# ADC.net
KiCad netlist of a schematic drawn in Altium Designer
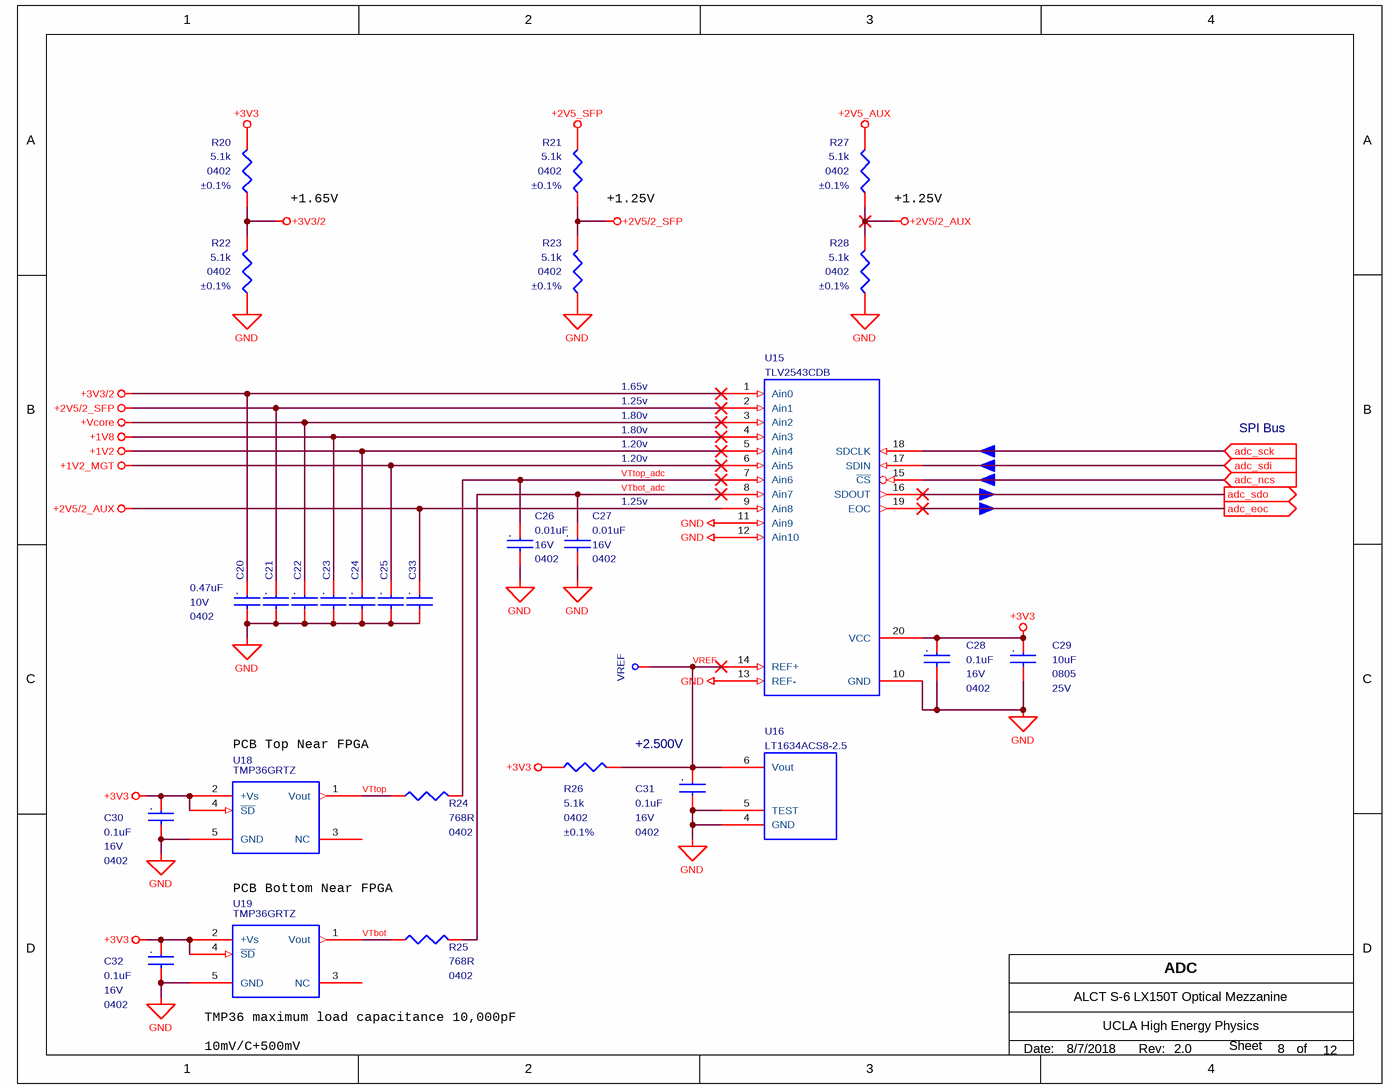
[diagram p0: ADC.SchDoc]

(export (version "E")
  (design (tool "Eeschema 10.0.6"))
  (components
    (comp (ref "C20")
      (value "0.47uF")
      (footprint "MC_S6/SM/C_0402_IPC")
      (description "CAP CER 0.47UF 10V X5R 0402")
      (fields
        (field (name "MANUFACTURER") "Murata Electronics North America")
        (field (name "MANUFACTURER PART NUMBER") "GRM155R61A474KE15J")
        (field (name "PACKAGE") "0402")
        (field (name "VOLTAGE - RATED") "10V")
      )
      (libsource (lib "ALCT_MEZ_SPARTAN6_Library") (part "GRM155R61A474KE15J"))
    )
    (comp (ref "C21")
      (value "0.47uF")
      (footprint "MC_S6/SM/C_0402_IPC")
      (description "CAP CER 0.47UF 10V X5R 0402")
      (fields
        (field (name "MANUFACTURER") "Murata Electronics North America")
        (field (name "MANUFACTURER PART NUMBER") "GRM155R61A474KE15J")
      )
      (libsource (lib "ALCT_MEZ_SPARTAN6_Library") (part "GRM155R61A474KE15J"))
    )
    (comp (ref "C22")
      (value "0.47uF")
      (footprint "MC_S6/SM/C_0402_IPC")
      (description "CAP CER 0.47UF 10V X5R 0402")
      (fields
        (field (name "MANUFACTURER") "Murata Electronics North America")
        (field (name "MANUFACTURER PART NUMBER") "GRM155R61A474KE15J")
      )
      (libsource (lib "ALCT_MEZ_SPARTAN6_Library") (part "GRM155R61A474KE15J"))
    )
    (comp (ref "C23")
      (value "0.47uF")
      (footprint "MC_S6/SM/C_0402_IPC")
      (description "CAP CER 0.47UF 10V X5R 0402")
      (fields
        (field (name "MANUFACTURER") "Murata Electronics North America")
        (field (name "MANUFACTURER PART NUMBER") "GRM155R61A474KE15J")
      )
      (libsource (lib "ALCT_MEZ_SPARTAN6_Library") (part "GRM155R61A474KE15J"))
    )
    (comp (ref "C24")
      (value "0.47uF")
      (footprint "MC_S6/SM/C_0402_IPC")
      (description "CAP CER 0.47UF 10V X5R 0402")
      (fields
        (field (name "MANUFACTURER") "Murata Electronics North America")
        (field (name "MANUFACTURER PART NUMBER") "GRM155R61A474KE15J")
      )
      (libsource (lib "ALCT_MEZ_SPARTAN6_Library") (part "GRM155R61A474KE15J"))
    )
    (comp (ref "C25")
      (value "0.47uF")
      (footprint "MC_S6/SM/C_0402_IPC")
      (description "CAP CER 0.47UF 10V X5R 0402")
      (fields
        (field (name "MANUFACTURER") "Murata Electronics North America")
        (field (name "MANUFACTURER PART NUMBER") "GRM155R61A474KE15J")
      )
      (libsource (lib "ALCT_MEZ_SPARTAN6_Library") (part "GRM155R61A474KE15J"))
    )
    (comp (ref "C26")
      (value "0.01uF")
      (footprint "MC_S6/SM/C_0402_IPC")
      (description "CAP CER 10nF 16V X7R 0402")
      (fields
        (field (name "MANUFACTURER") "KEMET")
        (field (name "MANUFACTURER PART NUMBER") "C0402C103K4RACTU")
        (field (name "VOLTAGE - RATED") "16V")
        (field (name "PACKAGE") "0402")
      )
      (libsource (lib "ALCT_MEZ_SPARTAN6_Library") (part "C0402C103K4RACTU"))
    )
    (comp (ref "C27")
      (value "0.01uF")
      (footprint "MC_S6/SM/C_0402_IPC")
      (description "CAP CER 10nF 16V X7R 0402")
      (fields
        (field (name "MANUFACTURER") "KEMET")
        (field (name "MANUFACTURER PART NUMBER") "C0402C103K4RACTU")
        (field (name "VOLTAGE - RATED") "16V")
        (field (name "PACKAGE") "0402")
      )
      (libsource (lib "ALCT_MEZ_SPARTAN6_Library") (part "C0402C103K4RACTU"))
    )
    (comp (ref "C28")
      (value "0.1uF")
      (footprint "MC_S6/SM/C_0402_IPC")
      (description "CAP CER 0.1UF 16V X7R 0402")
      (fields
        (field (name "MANUFACTURER") "KEMET")
        (field (name "MANUFACTURER PART NUMBER") "C0402C104K4RACTU")
        (field (name "PACKAGE") "0402")
        (field (name "VOLTAGE - RATED") "16V")
      )
      (libsource (lib "ALCT_MEZ_SPARTAN6_Library") (part "C0402C104K4RACTU"))
    )
    (comp (ref "C29")
      (value "10uF")
      (footprint "MC_S6/SM/C_0805_IPC")
      (description "CAP CER 10UF 25V X5R 0805")
      (fields
        (field (name "MANUFACTURER") "Murata Electronics North America")
        (field (name "MANUFACTURER PART NUMBER") "GRM21BR61E106KA73L")
        (field (name "VOLTAGE - RATED") "25V")
        (field (name "PACKAGE") "0805")
      )
      (libsource (lib "ALCT_MEZ_SPARTAN6_Library") (part "GRM21BR61E106KA73L"))
    )
    (comp (ref "C30")
      (value "0.1uF")
      (footprint "MC_S6/SM/C_0402_IPC")
      (description "CAP CER 0.1UF 16V X7R 0402")
      (fields
        (field (name "MANUFACTURER") "KEMET")
        (field (name "MANUFACTURER PART NUMBER") "C0402C104K4RACTU")
        (field (name "PACKAGE") "0402")
        (field (name "VOLTAGE - RATED") "16V")
      )
      (libsource (lib "ALCT_MEZ_SPARTAN6_Library") (part "C0402C104K4RACTU"))
    )
    (comp (ref "C31")
      (value "0.1uF")
      (footprint "MC_S6/SM/C_0402_IPC")
      (description "CAP CER 0.1UF 16V X7R 0402")
      (fields
        (field (name "MANUFACTURER") "KEMET")
        (field (name "MANUFACTURER PART NUMBER") "C0402C104K4RACTU")
        (field (name "PACKAGE") "0402")
        (field (name "VOLTAGE - RATED") "16V")
      )
      (libsource (lib "ALCT_MEZ_SPARTAN6_Library") (part "C0402C104K4RACTU"))
    )
    (comp (ref "C32")
      (value "0.1uF")
      (footprint "MC_S6/SM/C_0402_IPC")
      (description "CAP CER 0.1UF 16V X7R 0402")
      (fields
        (field (name "MANUFACTURER") "KEMET")
        (field (name "MANUFACTURER PART NUMBER") "C0402C104K4RACTU")
        (field (name "PACKAGE") "0402")
        (field (name "VOLTAGE - RATED") "16V")
      )
      (libsource (lib "ALCT_MEZ_SPARTAN6_Library") (part "C0402C104K4RACTU"))
    )
    (comp (ref "C33")
      (value "0.47uF")
      (footprint "MC_S6/SM/C_0402_IPC")
      (description "CAP CER 0.47UF 10V X5R 0402")
      (fields
        (field (name "MANUFACTURER") "Murata Electronics North America")
        (field (name "MANUFACTURER PART NUMBER") "GRM155R61A474KE15J")
      )
      (libsource (lib "ALCT_MEZ_SPARTAN6_Library") (part "GRM155R61A474KE15J"))
    )
    (comp (ref "R20")
      (value "5.1k")
      (footprint "MC_S6/SM/R_0402_IPC")
      (description "RES SMD 5.1K OHM 0.1% 1/16W 0402")
      (fields
        (field (name "TOLERANCE") "±0.1%")
        (field (name "MANUFACTURER") "Panasonic Electronic Components")
        (field (name "MANUFACTURER PART NUMBER") "ERA-2AEB512X")
        (field (name "SUPPLIER DEVICE PACKAGE") "0402")
      )
      (libsource (lib "ALCT_MEZ_SPARTAN6_Library") (part "ERA-2AEB512X"))
    )
    (comp (ref "R21")
      (value "5.1k")
      (footprint "MC_S6/SM/R_0402_IPC")
      (description "RES SMD 5.1K OHM 0.1% 1/16W 0402")
      (fields
        (field (name "TOLERANCE") "±0.1%")
        (field (name "MANUFACTURER") "Panasonic Electronic Components")
        (field (name "MANUFACTURER PART NUMBER") "ERA-2AEB512X")
        (field (name "SUPPLIER DEVICE PACKAGE") "0402")
      )
      (libsource (lib "ALCT_MEZ_SPARTAN6_Library") (part "ERA-2AEB512X"))
    )
    (comp (ref "R22")
      (value "5.1k")
      (footprint "MC_S6/SM/R_0402_IPC")
      (description "RES SMD 5.1K OHM 0.1% 1/16W 0402")
      (fields
        (field (name "TOLERANCE") "±0.1%")
        (field (name "MANUFACTURER") "Panasonic Electronic Components")
        (field (name "MANUFACTURER PART NUMBER") "ERA-2AEB512X")
        (field (name "SUPPLIER DEVICE PACKAGE") "0402")
      )
      (libsource (lib "ALCT_MEZ_SPARTAN6_Library") (part "ERA-2AEB512X"))
    )
    (comp (ref "R23")
      (value "5.1k")
      (footprint "MC_S6/SM/R_0402_IPC")
      (description "RES SMD 5.1K OHM 0.1% 1/16W 0402")
      (fields
        (field (name "TOLERANCE") "±0.1%")
        (field (name "MANUFACTURER") "Panasonic Electronic Components")
        (field (name "MANUFACTURER PART NUMBER") "ERA-2AEB512X")
        (field (name "SUPPLIER DEVICE PACKAGE") "0402")
      )
      (libsource (lib "ALCT_MEZ_SPARTAN6_Library") (part "ERA-2AEB512X"))
    )
    (comp (ref "R24")
      (value "768R")
      (footprint "MC_S6/SM/R_0402_IPC")
      (description "RES SMD 768 OHM 5.0% 1/10W 0402")
      (fields
        (field (name "MANUFACTURER") "Panasonic Electronic Components")
        (field (name "MANUFACTURER PART NUMBER") "ERJ-2RKF7680X")
        (field (name "SUPPLIER DEVICE PACKAGE") "0402")
      )
      (libsource (lib "ALCT_MEZ_SPARTAN6_Library") (part "ERJ-2RKF7680X"))
    )
    (comp (ref "R25")
      (value "768R")
      (footprint "MC_S6/SM/R_0402_IPC")
      (description "RES SMD 768 OHM 5.0% 1/10W 0402")
      (fields
        (field (name "TOLERANCE") "±1%")
        (field (name "MANUFACTURER") "Panasonic Electronic Components")
        (field (name "SUPPLIER DEVICE PACKAGE") "0402")
      )
      (libsource (lib "ALCT_MEZ_SPARTAN6_Library") (part "ERJ-2RKF7680X"))
    )
    (comp (ref "R26")
      (value "5.1k")
      (footprint "MC_S6/SM/R_0402_IPC")
      (description "RES SMD 5.1K OHM 0.1% 1/16W 0402")
      (fields
        (field (name "TOLERANCE") "±0.1%")
        (field (name "MANUFACTURER") "Panasonic Electronic Components")
        (field (name "MANUFACTURER PART NUMBER") "ERA-2AEB512X")
        (field (name "SUPPLIER DEVICE PACKAGE") "0402")
      )
      (libsource (lib "ALCT_MEZ_SPARTAN6_Library") (part "ERA-2AEB512X"))
    )
    (comp (ref "R27")
      (value "5.1k")
      (footprint "MC_S6/SM/R_0402_IPC")
      (description "RES SMD 5.1K OHM 0.1% 1/16W 0402")
      (fields
        (field (name "TOLERANCE") "±0.1%")
        (field (name "MANUFACTURER") "Panasonic Electronic Components")
        (field (name "MANUFACTURER PART NUMBER") "ERA-2AEB512X")
        (field (name "SUPPLIER DEVICE PACKAGE") "0402")
      )
      (libsource (lib "ALCT_MEZ_SPARTAN6_Library") (part "ERA-2AEB512X"))
    )
    (comp (ref "R28")
      (value "5.1k")
      (footprint "MC_S6/SM/R_0402_IPC")
      (description "RES SMD 5.1K OHM 0.1% 1/16W 0402")
      (fields
        (field (name "TOLERANCE") "±0.1%")
        (field (name "MANUFACTURER") "Panasonic Electronic Components")
        (field (name "MANUFACTURER PART NUMBER") "ERA-2AEB512X")
        (field (name "SUPPLIER DEVICE PACKAGE") "0402")
      )
      (libsource (lib "ALCT_MEZ_SPARTAN6_Library") (part "ERA-2AEB512X"))
    )
    (comp (ref "U15")
      (value "TLV2543CDB")
      (footprint "MC_S6/SM/ADC_DB20")
      (description "IC SERIAL OUT A/D 11-CH 20-SSOP")
      (fields
        (field (name "MANUFACTURER") "Texas Instruments")
        (field (name "MANUFACTURER PART NUMBER") "TLV2543CDBR")
      )
      (libsource (lib "ALCT_MEZ_SPARTAN6_Library") (part "TLV2543CDB"))
    )
    (comp (ref "U16")
      (value "LT1634ACS8-2.5")
      (footprint "MC_S6/SM/LT1634_SOIC8")
      (description "IC VREF SHUNT 2.5V 8SOIC")
      (fields
        (field (name "MANUFACTURER") "Linear Technology")
        (field (name "MANUFACTURER PART NUMBER") "LT1634ACS8-2.5#PBF")
      )
      (libsource (lib "ALCT_MEZ_SPARTAN6_Library") (part "LT1634_2.5V"))
    )
    (comp (ref "U18")
      (value "TMP36GRTZ")
      (footprint "MC_S6/SM/SOT23_RJ5")
      (description "SENSOR TEMP ANLG VOLT SOT-23-5")
      (fields
        (field (name "MANUFACTURER") "Analog Devices Inc.")
        (field (name "MANUFACTURER PART NUMBER") "TMP36FSZ-REEL")
      )
      (libsource (lib "ALCT_MEZ_SPARTAN6_Library") (part "TMP36GRTZ"))
    )
    (comp (ref "U19")
      (value "TMP36GRTZ")
      (footprint "MC_S6/SM/SOT23_RJ5")
      (description "SENSOR TEMP ANLG VOLT SOT-23-5")
      (fields
        (field (name "MANUFACTURER") "Analog Devices Inc.")
        (field (name "MANUFACTURER PART NUMBER") "TMP36FSZ-REEL")
      )
      (libsource (lib "ALCT_MEZ_SPARTAN6_Library") (part "TMP36GRTZ"))
    )
    (comp (ref "VREF")
      (value "Test Point Via")
      (footprint "MC_S6/TH/TPVIA")
      (libsource (lib "ALCT_MEZ_SPARTAN6_Library") (part "TPVIA"))
    )
  )
  (nets
    (net (code "1") (name "+1V2") (class "Default")
      (node (ref "C24") (pin "1") (pinfunction "1_1") (pintype "passive"))
      (node (ref "U15") (pin "5") (pinfunction "Ain4_5") (pintype "input"))
    )
    (net (code "2") (name "+1V2_MGT") (class "Default")
      (node (ref "C25") (pin "1") (pinfunction "1_1") (pintype "passive"))
      (node (ref "U15") (pin "6") (pinfunction "Ain5_6") (pintype "input"))
    )
    (net (code "3") (name "+1V8") (class "Default")
      (node (ref "C23") (pin "1") (pinfunction "1_1") (pintype "passive"))
      (node (ref "U15") (pin "4") (pinfunction "Ain3_4") (pintype "input"))
    )
    (net (code "4") (name "+2V5_AUX") (class "Default")
      (node (ref "R27") (pin "1") (pinfunction "1_1") (pintype "passive"))
    )
    (net (code "5") (name "+2V5_SFP") (class "Default")
      (node (ref "R21") (pin "1") (pinfunction "1_1") (pintype "passive"))
    )
    (net (code "6") (name "+2V5{slash}2_AUX") (class "Default")
      (node (ref "C33") (pin "1") (pinfunction "1_1") (pintype "passive"))
      (node (ref "R27") (pin "2") (pinfunction "2_2") (pintype "passive"))
      (node (ref "R28") (pin "1") (pinfunction "1_1") (pintype "passive"))
      (node (ref "U15") (pin "9") (pinfunction "Ain8_9") (pintype "input"))
    )
    (net (code "7") (name "+2V5{slash}2_SFP") (class "Default")
      (node (ref "C21") (pin "1") (pinfunction "1_1") (pintype "passive"))
      (node (ref "R21") (pin "2") (pinfunction "2_2") (pintype "passive"))
      (node (ref "R23") (pin "1") (pinfunction "1_1") (pintype "passive"))
      (node (ref "U15") (pin "2") (pinfunction "Ain1_2") (pintype "input"))
    )
    (net (code "8") (name "+3V3") (class "Default")
      (node (ref "C28") (pin "1") (pinfunction "1_1") (pintype "passive"))
      (node (ref "C29") (pin "1") (pinfunction "1_1") (pintype "passive"))
      (node (ref "C30") (pin "1") (pinfunction "1_1") (pintype "passive"))
      (node (ref "C32") (pin "1") (pinfunction "1_1") (pintype "passive"))
      (node (ref "R20") (pin "1") (pinfunction "1_1") (pintype "passive"))
      (node (ref "R26") (pin "1") (pinfunction "1_1") (pintype "passive"))
      (node (ref "U15") (pin "20") (pinfunction "VCC_20") (pintype "power_in"))
      (node (ref "U18") (pin "2") (pinfunction "+Vs_2") (pintype "power_in"))
      (node (ref "U18") (pin "4") (pinfunction "~{SD}_4") (pintype "input"))
      (node (ref "U19") (pin "2") (pinfunction "+Vs_2") (pintype "power_in"))
      (node (ref "U19") (pin "4") (pinfunction "~{SD}_4") (pintype "input"))
    )
    (net (code "9") (name "+3V3{slash}2") (class "Default")
      (node (ref "C20") (pin "1") (pinfunction "1_1") (pintype "passive"))
      (node (ref "R20") (pin "2") (pinfunction "2_2") (pintype "passive"))
      (node (ref "R22") (pin "1") (pinfunction "1_1") (pintype "passive"))
      (node (ref "U15") (pin "1") (pinfunction "Ain0_1") (pintype "input"))
    )
    (net (code "10") (name "+Vcore") (class "Default")
      (node (ref "C22") (pin "1") (pinfunction "1_1") (pintype "passive"))
      (node (ref "U15") (pin "3") (pinfunction "Ain2_3") (pintype "input"))
    )
    (net (code "11") (name "/VREF") (class "Default")
      (node (ref "C31") (pin "1") (pinfunction "1_1") (pintype "passive"))
      (node (ref "R26") (pin "2") (pinfunction "2_2") (pintype "passive"))
      (node (ref "U15") (pin "14") (pinfunction "REF+_14") (pintype "input"))
      (node (ref "U16") (pin "6") (pinfunction "Vout_6") (pintype "passive"))
      (node (ref "VREF") (pin "1") (pinfunction "In_1") (pintype "passive"))
    )
    (net (code "12") (name "/VTbot") (class "Default")
      (node (ref "R25") (pin "1") (pinfunction "1_1") (pintype "passive"))
      (node (ref "U19") (pin "1") (pinfunction "Vout_1") (pintype "output"))
    )
    (net (code "13") (name "/VTbot_adc") (class "Default")
      (node (ref "C27") (pin "1") (pinfunction "1_1") (pintype "passive"))
      (node (ref "R25") (pin "2") (pinfunction "2_2") (pintype "passive"))
      (node (ref "U15") (pin "8") (pinfunction "Ain7_8") (pintype "input"))
    )
    (net (code "14") (name "/VTtop") (class "Default")
      (node (ref "R24") (pin "1") (pinfunction "1_1") (pintype "passive"))
      (node (ref "U18") (pin "1") (pinfunction "Vout_1") (pintype "output"))
    )
    (net (code "15") (name "/VTtop_adc") (class "Default")
      (node (ref "C26") (pin "1") (pinfunction "1_1") (pintype "passive"))
      (node (ref "R24") (pin "2") (pinfunction "2_2") (pintype "passive"))
      (node (ref "U15") (pin "7") (pinfunction "Ain6_7") (pintype "input"))
    )
    (net (code "16") (name "/adc_eoc") (class "Default")
      (node (ref "U15") (pin "19") (pinfunction "EOC_19") (pintype "output+no_connect"))
    )
    (net (code "17") (name "/adc_ncs") (class "Default")
      (node (ref "U15") (pin "15") (pinfunction "~{CS}_15") (pintype "input"))
    )
    (net (code "18") (name "/adc_sck") (class "Default")
      (node (ref "U15") (pin "18") (pinfunction "SDCLK_18") (pintype "input"))
    )
    (net (code "19") (name "/adc_sdi") (class "Default")
      (node (ref "U15") (pin "17") (pinfunction "SDIN_17") (pintype "input"))
    )
    (net (code "20") (name "/adc_sdo") (class "Default")
      (node (ref "U15") (pin "16") (pinfunction "SDOUT_16") (pintype "output+no_connect"))
    )
    (net (code "21") (name "GND") (class "Default")
      (node (ref "C20") (pin "2") (pinfunction "2_2") (pintype "passive"))
      (node (ref "C21") (pin "2") (pinfunction "2_2") (pintype "passive"))
      (node (ref "C22") (pin "2") (pinfunction "2_2") (pintype "passive"))
      (node (ref "C23") (pin "2") (pinfunction "2_2") (pintype "passive"))
      (node (ref "C24") (pin "2") (pinfunction "2_2") (pintype "passive"))
      (node (ref "C25") (pin "2") (pinfunction "2_2") (pintype "passive"))
      (node (ref "C26") (pin "2") (pinfunction "2_2") (pintype "passive"))
      (node (ref "C27") (pin "2") (pinfunction "2_2") (pintype "passive"))
      (node (ref "C28") (pin "2") (pinfunction "2_2") (pintype "passive"))
      (node (ref "C29") (pin "2") (pinfunction "2_2") (pintype "passive"))
      (node (ref "C30") (pin "2") (pinfunction "2_2") (pintype "passive"))
      (node (ref "C31") (pin "2") (pinfunction "2_2") (pintype "passive"))
      (node (ref "C32") (pin "2") (pinfunction "2_2") (pintype "passive"))
      (node (ref "C33") (pin "2") (pinfunction "2_2") (pintype "passive"))
      (node (ref "R22") (pin "2") (pinfunction "2_2") (pintype "passive"))
      (node (ref "R23") (pin "2") (pinfunction "2_2") (pintype "passive"))
      (node (ref "R28") (pin "2") (pinfunction "2_2") (pintype "passive"))
      (node (ref "U15") (pin "10") (pinfunction "GND_10") (pintype "power_in"))
      (node (ref "U15") (pin "11") (pinfunction "Ain9_11") (pintype "input"))
      (node (ref "U15") (pin "12") (pinfunction "Ain10_12") (pintype "input"))
      (node (ref "U15") (pin "13") (pinfunction "REF-_13") (pintype "input"))
      (node (ref "U16") (pin "4") (pinfunction "GND_4") (pintype "power_in"))
      (node (ref "U16") (pin "5") (pinfunction "TEST_5") (pintype "passive"))
      (node (ref "U18") (pin "5") (pinfunction "GND_5") (pintype "power_in"))
      (node (ref "U19") (pin "5") (pinfunction "GND_5") (pintype "power_in"))
    )
    (net (code "22") (name "unconnected-(U18-NC-Pad3)") (class "Default")
      (node (ref "U18") (pin "3") (pinfunction "NC_3") (pintype "passive"))
    )
    (net (code "23") (name "unconnected-(U19-NC-Pad3)") (class "Default")
      (node (ref "U19") (pin "3") (pinfunction "NC_3") (pintype "passive"))
    )
  )
)
